# MCP23017.net
KiCad netlist of a schematic drawn in EAGLE
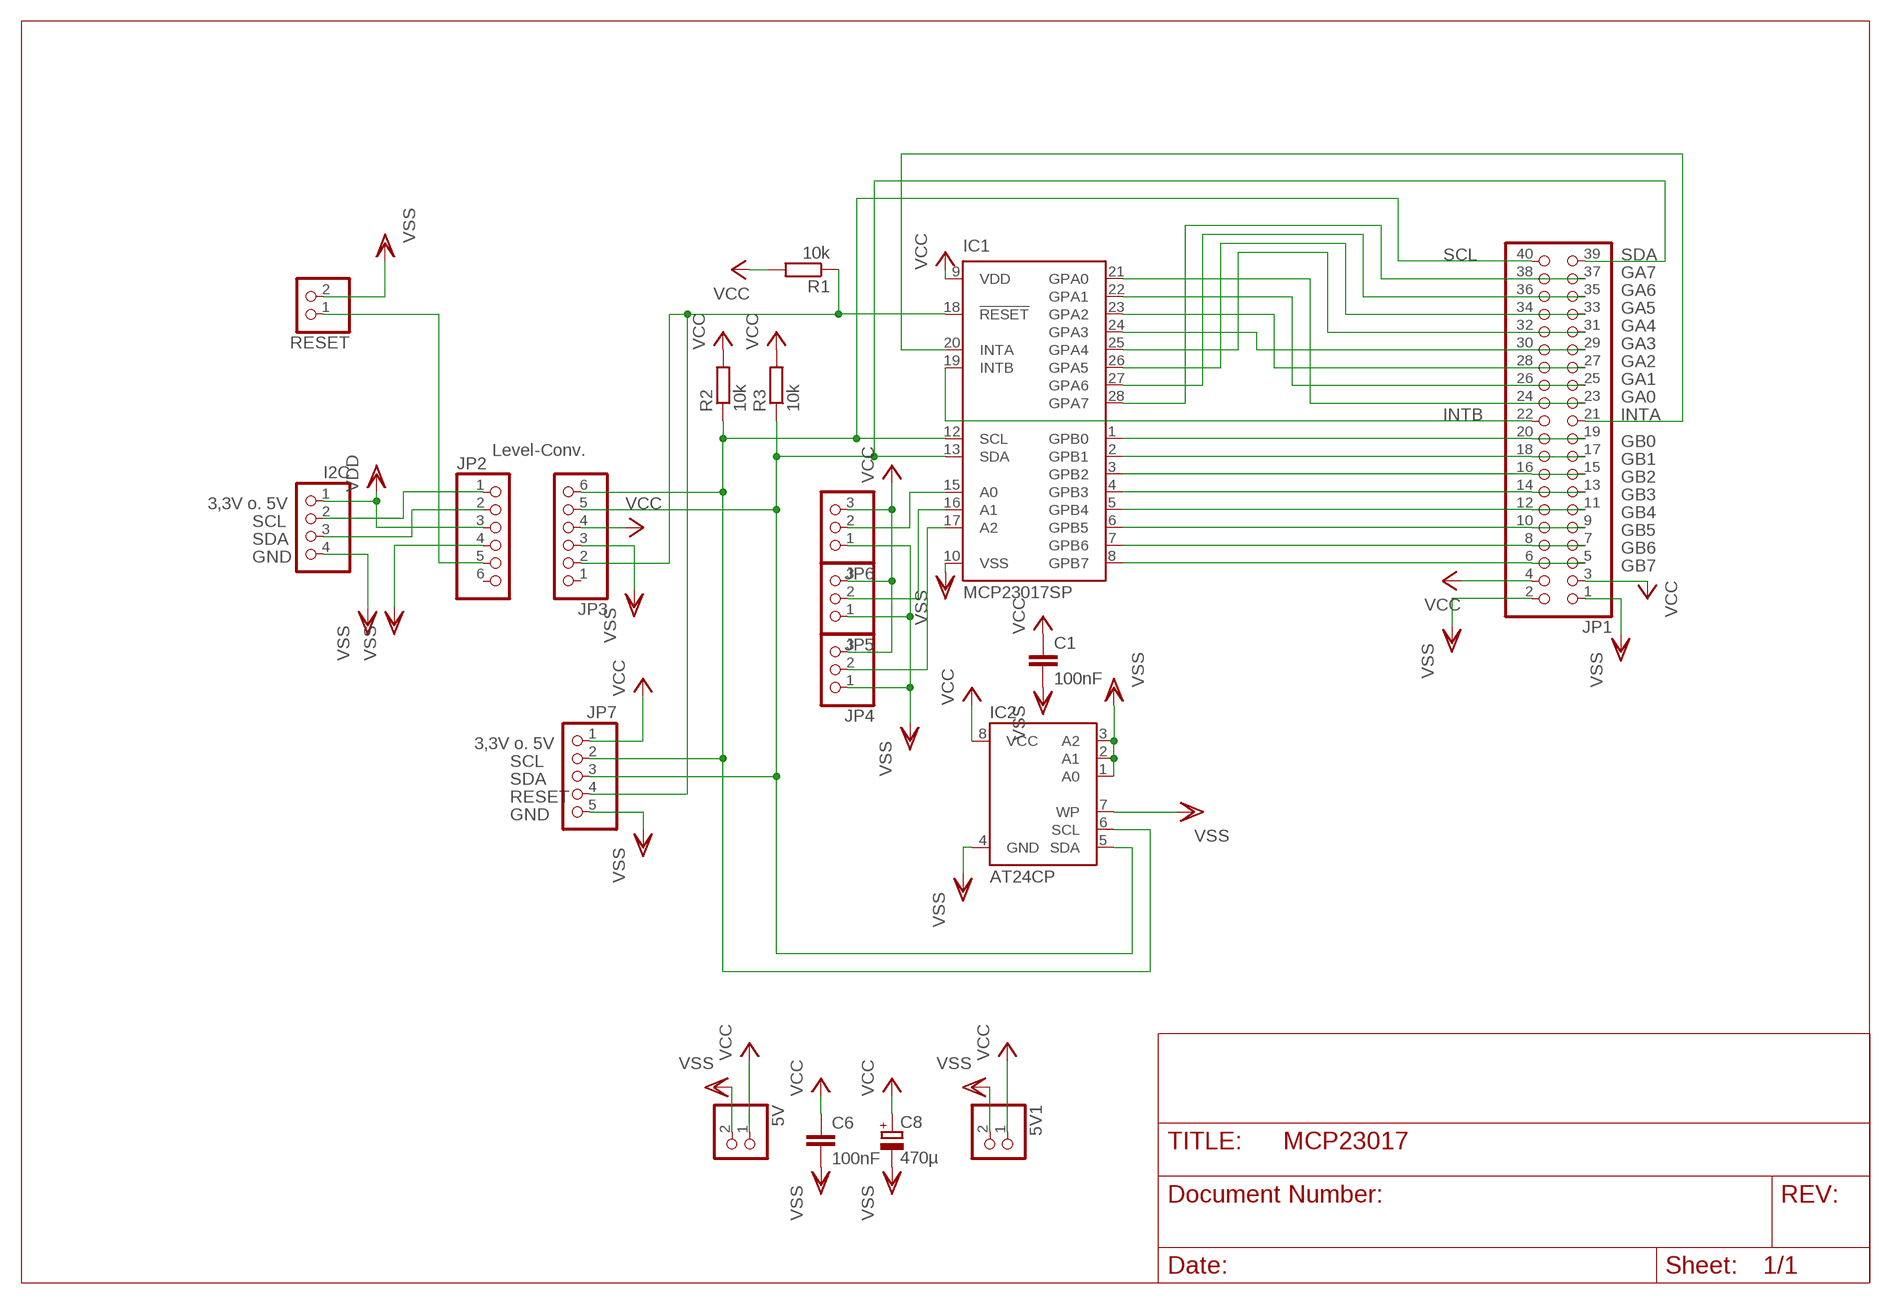
[diagram p0: schematic, sheet 1]

(export (version "E")
  (design (tool "Eeschema 10.0.6"))
  (components
    (comp (ref "5V")
      (value "PINHD-1X2")
      (footprint "eagle-import:1X02")
      (libsource (lib "eagle-import") (part "PINHD-1X2"))
    )
    (comp (ref "5V1")
      (value "PINHD-1X2")
      (footprint "eagle-import:1X02")
      (libsource (lib "eagle-import") (part "PINHD-1X2"))
    )
    (comp (ref "C1")
      (value "100nF")
      (footprint "eagle-import:C025-030X050")
      (libsource (lib "eagle-import") (part "C-EU025-030X050"))
    )
    (comp (ref "C6")
      (value "100nF")
      (footprint "eagle-import:C025-030X050")
      (libsource (lib "eagle-import") (part "C-EU025-030X050"))
    )
    (comp (ref "C8")
      (value "470µ")
      (footprint "eagle-import:E3,5-10")
      (libsource (lib "eagle-import") (part "CPOL-EUE3.5-10"))
    )
    (comp (ref "I2C")
      (value "PINHD-1X4")
      (footprint "eagle-import:1X04")
      (libsource (lib "eagle-import") (part "PINHD-1X4"))
    )
    (comp (ref "IC1")
      (value "MCP23017SP")
      (footprint "eagle-import:DIL28-3")
      (fields (field (name "MF") "MICROCHIP") (field (name "MPN") "MCP23017-E/SP"))
      (libsource (lib "eagle-import") (part "MCP23017SP"))
    )
    (comp (ref "IC2")
      (value "AT24CP")
      (footprint "eagle-import:DIL08")
      (fields (field (name "MPN") "AT24C1024BW-SH-B"))
      (libsource (lib "eagle-import") (part "AT24CP"))
    )
    (comp (ref "JP1")
      (value "PINHD-2X20")
      (footprint "eagle-import:2X20")
      (libsource (lib "eagle-import") (part "PINHD-2X20"))
    )
    (comp (ref "JP2")
      (value "PINHD-1X6")
      (footprint "eagle-import:1X06")
      (libsource (lib "eagle-import") (part "PINHD-1X6"))
    )
    (comp (ref "JP3")
      (value "PINHD-1X6")
      (footprint "eagle-import:1X06")
      (libsource (lib "eagle-import") (part "PINHD-1X6"))
    )
    (comp (ref "JP4")
      (value "PINHD-1X3")
      (footprint "eagle-import:1X03")
      (libsource (lib "eagle-import") (part "PINHD-1X3"))
    )
    (comp (ref "JP5")
      (value "PINHD-1X3")
      (footprint "eagle-import:1X03")
      (libsource (lib "eagle-import") (part "PINHD-1X3"))
    )
    (comp (ref "JP6")
      (value "PINHD-1X3")
      (footprint "eagle-import:1X03")
      (libsource (lib "eagle-import") (part "PINHD-1X3"))
    )
    (comp (ref "JP7")
      (value "PINHD-1X5")
      (footprint "eagle-import:1X05")
      (libsource (lib "eagle-import") (part "PINHD-1X5"))
    )
    (comp (ref "R1")
      (value "10k")
      (footprint "eagle-import:0207_10")
      (libsource (lib "eagle-import") (part "R-EU_0207/10"))
    )
    (comp (ref "R2")
      (value "10k")
      (footprint "eagle-import:0207_10")
      (libsource (lib "eagle-import") (part "R-EU_0207/10"))
    )
    (comp (ref "R3")
      (value "10k")
      (footprint "eagle-import:0207_10")
      (libsource (lib "eagle-import") (part "R-EU_0207/10"))
    )
    (comp (ref "RESET")
      (value "PINHD-1X2")
      (footprint "eagle-import:1X02")
      (libsource (lib "eagle-import") (part "PINHD-1X2"))
    )
  )
  (nets
    (net (code "1") (name "Net-(I2C-Pad2)") (class "Default")
      (node (ref "I2C") (pin "2") (pinfunction "2_2") (pintype "passive"))
      (node (ref "JP2") (pin "1") (pinfunction "1_1") (pintype "passive"))
    )
    (net (code "2") (name "Net-(I2C-Pad3)") (class "Default")
      (node (ref "I2C") (pin "3") (pinfunction "3_3") (pintype "passive"))
      (node (ref "JP2") (pin "2") (pinfunction "2_2") (pintype "passive"))
    )
    (net (code "3") (name "Net-(IC1-A0)") (class "Default")
      (node (ref "IC1") (pin "15") (pinfunction "A0_15") (pintype "input"))
      (node (ref "JP6") (pin "2") (pinfunction "2_2") (pintype "passive"))
    )
    (net (code "4") (name "Net-(IC1-A1)") (class "Default")
      (node (ref "IC1") (pin "16") (pinfunction "A1_16") (pintype "input"))
      (node (ref "JP5") (pin "2") (pinfunction "2_2") (pintype "passive"))
    )
    (net (code "5") (name "Net-(IC1-A2)") (class "Default")
      (node (ref "IC1") (pin "17") (pinfunction "A2_17") (pintype "input"))
      (node (ref "JP4") (pin "2") (pinfunction "2_2") (pintype "passive"))
    )
    (net (code "6") (name "Net-(IC1-GPA0)") (class "Default")
      (node (ref "IC1") (pin "21") (pinfunction "GPA0_21") (pintype "bidirectional"))
      (node (ref "JP1") (pin "23") (pinfunction "23_23") (pintype "passive"))
      (node (ref "JP1") (pin "24") (pinfunction "24_24") (pintype "passive"))
    )
    (net (code "7") (name "Net-(IC1-GPA1)") (class "Default")
      (node (ref "IC1") (pin "22") (pinfunction "GPA1_22") (pintype "bidirectional"))
      (node (ref "JP1") (pin "25") (pinfunction "25_25") (pintype "passive"))
      (node (ref "JP1") (pin "26") (pinfunction "26_26") (pintype "passive"))
    )
    (net (code "8") (name "Net-(IC1-GPA2)") (class "Default")
      (node (ref "IC1") (pin "23") (pinfunction "GPA2_23") (pintype "bidirectional"))
      (node (ref "JP1") (pin "27") (pinfunction "27_27") (pintype "passive"))
      (node (ref "JP1") (pin "28") (pinfunction "28_28") (pintype "passive"))
    )
    (net (code "9") (name "Net-(IC1-GPA3)") (class "Default")
      (node (ref "IC1") (pin "24") (pinfunction "GPA3_24") (pintype "bidirectional"))
      (node (ref "JP1") (pin "29") (pinfunction "29_29") (pintype "passive"))
      (node (ref "JP1") (pin "30") (pinfunction "30_30") (pintype "passive"))
    )
    (net (code "10") (name "Net-(IC1-GPA4)") (class "Default")
      (node (ref "IC1") (pin "25") (pinfunction "GPA4_25") (pintype "bidirectional"))
      (node (ref "JP1") (pin "31") (pinfunction "31_31") (pintype "passive"))
      (node (ref "JP1") (pin "32") (pinfunction "32_32") (pintype "passive"))
    )
    (net (code "11") (name "Net-(IC1-GPA5)") (class "Default")
      (node (ref "IC1") (pin "26") (pinfunction "GPA5_26") (pintype "bidirectional"))
      (node (ref "JP1") (pin "33") (pinfunction "33_33") (pintype "passive"))
      (node (ref "JP1") (pin "34") (pinfunction "34_34") (pintype "passive"))
    )
    (net (code "12") (name "Net-(IC1-GPA6)") (class "Default")
      (node (ref "IC1") (pin "27") (pinfunction "GPA6_27") (pintype "bidirectional"))
      (node (ref "JP1") (pin "35") (pinfunction "35_35") (pintype "passive"))
      (node (ref "JP1") (pin "36") (pinfunction "36_36") (pintype "passive"))
    )
    (net (code "13") (name "Net-(IC1-GPA7)") (class "Default")
      (node (ref "IC1") (pin "28") (pinfunction "GPA7_28") (pintype "bidirectional"))
      (node (ref "JP1") (pin "37") (pinfunction "37_37") (pintype "passive"))
      (node (ref "JP1") (pin "38") (pinfunction "38_38") (pintype "passive"))
    )
    (net (code "14") (name "Net-(IC1-GPB0)") (class "Default")
      (node (ref "IC1") (pin "1") (pinfunction "GPB0_1") (pintype "bidirectional"))
      (node (ref "JP1") (pin "19") (pinfunction "19_19") (pintype "passive"))
      (node (ref "JP1") (pin "20") (pinfunction "20_20") (pintype "passive"))
    )
    (net (code "15") (name "Net-(IC1-GPB1)") (class "Default")
      (node (ref "IC1") (pin "2") (pinfunction "GPB1_2") (pintype "bidirectional"))
      (node (ref "JP1") (pin "17") (pinfunction "17_17") (pintype "passive"))
      (node (ref "JP1") (pin "18") (pinfunction "18_18") (pintype "passive"))
    )
    (net (code "16") (name "Net-(IC1-GPB2)") (class "Default")
      (node (ref "IC1") (pin "3") (pinfunction "GPB2_3") (pintype "bidirectional"))
      (node (ref "JP1") (pin "15") (pinfunction "15_15") (pintype "passive"))
      (node (ref "JP1") (pin "16") (pinfunction "16_16") (pintype "passive"))
    )
    (net (code "17") (name "Net-(IC1-GPB3)") (class "Default")
      (node (ref "IC1") (pin "4") (pinfunction "GPB3_4") (pintype "bidirectional"))
      (node (ref "JP1") (pin "13") (pinfunction "13_13") (pintype "passive"))
      (node (ref "JP1") (pin "14") (pinfunction "14_14") (pintype "passive"))
    )
    (net (code "18") (name "Net-(IC1-GPB4)") (class "Default")
      (node (ref "IC1") (pin "5") (pinfunction "GPB4_5") (pintype "bidirectional"))
      (node (ref "JP1") (pin "11") (pinfunction "11_11") (pintype "passive"))
      (node (ref "JP1") (pin "12") (pinfunction "12_12") (pintype "passive"))
    )
    (net (code "19") (name "Net-(IC1-GPB5)") (class "Default")
      (node (ref "IC1") (pin "6") (pinfunction "GPB5_6") (pintype "bidirectional"))
      (node (ref "JP1") (pin "10") (pinfunction "10_10") (pintype "passive"))
      (node (ref "JP1") (pin "9") (pinfunction "9_9") (pintype "passive"))
    )
    (net (code "20") (name "Net-(IC1-GPB6)") (class "Default")
      (node (ref "IC1") (pin "7") (pinfunction "GPB6_7") (pintype "bidirectional"))
      (node (ref "JP1") (pin "7") (pinfunction "7_7") (pintype "passive"))
      (node (ref "JP1") (pin "8") (pinfunction "8_8") (pintype "passive"))
    )
    (net (code "21") (name "Net-(IC1-GPB7)") (class "Default")
      (node (ref "IC1") (pin "8") (pinfunction "GPB7_8") (pintype "bidirectional"))
      (node (ref "JP1") (pin "5") (pinfunction "5_5") (pintype "passive"))
      (node (ref "JP1") (pin "6") (pinfunction "6_6") (pintype "passive"))
    )
    (net (code "22") (name "Net-(IC1-INTA)") (class "Default")
      (node (ref "IC1") (pin "20") (pinfunction "INTA_20") (pintype "output"))
      (node (ref "JP1") (pin "21") (pinfunction "21_21") (pintype "passive"))
    )
    (net (code "23") (name "Net-(IC1-INTB)") (class "Default")
      (node (ref "IC1") (pin "19") (pinfunction "INTB_19") (pintype "output"))
      (node (ref "JP1") (pin "22") (pinfunction "22_22") (pintype "passive"))
    )
    (net (code "24") (name "Net-(IC1-SCL)") (class "Default")
      (node (ref "IC1") (pin "12") (pinfunction "SCL_12") (pintype "input"))
      (node (ref "IC2") (pin "6") (pinfunction "SCL_6") (pintype "bidirectional"))
      (node (ref "JP1") (pin "40") (pinfunction "40_40") (pintype "passive"))
      (node (ref "JP3") (pin "6") (pinfunction "6_6") (pintype "passive"))
      (node (ref "JP7") (pin "2") (pinfunction "2_2") (pintype "passive"))
      (node (ref "R2") (pin "1") (pinfunction "1_1") (pintype "passive"))
    )
    (net (code "25") (name "Net-(IC1-SDA)") (class "Default")
      (node (ref "IC1") (pin "13") (pinfunction "SDA_13") (pintype "bidirectional"))
      (node (ref "IC2") (pin "5") (pinfunction "SDA_5") (pintype "bidirectional"))
      (node (ref "JP1") (pin "39") (pinfunction "39_39") (pintype "passive"))
      (node (ref "JP3") (pin "5") (pinfunction "5_5") (pintype "passive"))
      (node (ref "JP7") (pin "3") (pinfunction "3_3") (pintype "passive"))
      (node (ref "R3") (pin "1") (pinfunction "1_1") (pintype "passive"))
    )
    (net (code "26") (name "Net-(IC1-~{RESET})") (class "Default")
      (node (ref "IC1") (pin "18") (pinfunction "~{RESET}_18") (pintype "input"))
      (node (ref "JP3") (pin "2") (pinfunction "2_2") (pintype "passive"))
      (node (ref "JP7") (pin "4") (pinfunction "4_4") (pintype "passive"))
      (node (ref "R1") (pin "1") (pinfunction "1_1") (pintype "passive"))
    )
    (net (code "27") (name "Net-(JP2-Pad5)") (class "Default")
      (node (ref "JP2") (pin "5") (pinfunction "5_5") (pintype "passive"))
      (node (ref "RESET") (pin "1") (pinfunction "1_1") (pintype "passive"))
    )
    (net (code "28") (name "VCC") (class "Default")
      (node (ref "5V") (pin "1") (pinfunction "1_1") (pintype "passive"))
      (node (ref "5V1") (pin "1") (pinfunction "1_1") (pintype "passive"))
      (node (ref "C1") (pin "1") (pinfunction "1_1") (pintype "passive"))
      (node (ref "C6") (pin "1") (pinfunction "1_1") (pintype "passive"))
      (node (ref "C8") (pin "+") (pinfunction "+_+") (pintype "passive"))
      (node (ref "IC1") (pin "9") (pinfunction "VDD_9") (pintype "power_in"))
      (node (ref "IC2") (pin "8") (pinfunction "VCC_8") (pintype "power_in"))
      (node (ref "JP1") (pin "3") (pinfunction "3_3") (pintype "passive"))
      (node (ref "JP1") (pin "4") (pinfunction "4_4") (pintype "passive"))
      (node (ref "JP3") (pin "4") (pinfunction "4_4") (pintype "passive"))
      (node (ref "JP4") (pin "3") (pinfunction "3_3") (pintype "passive"))
      (node (ref "JP5") (pin "3") (pinfunction "3_3") (pintype "passive"))
      (node (ref "JP6") (pin "3") (pinfunction "3_3") (pintype "passive"))
      (node (ref "JP7") (pin "1") (pinfunction "1_1") (pintype "passive"))
      (node (ref "R1") (pin "2") (pinfunction "2_2") (pintype "passive"))
      (node (ref "R2") (pin "2") (pinfunction "2_2") (pintype "passive"))
      (node (ref "R3") (pin "2") (pinfunction "2_2") (pintype "passive"))
    )
    (net (code "29") (name "VDD") (class "Default")
      (node (ref "I2C") (pin "1") (pinfunction "1_1") (pintype "passive"))
      (node (ref "JP2") (pin "3") (pinfunction "3_3") (pintype "passive"))
    )
    (net (code "30") (name "VSS") (class "Default")
      (node (ref "5V") (pin "2") (pinfunction "2_2") (pintype "passive"))
      (node (ref "5V1") (pin "2") (pinfunction "2_2") (pintype "passive"))
      (node (ref "C1") (pin "2") (pinfunction "2_2") (pintype "passive"))
      (node (ref "C6") (pin "2") (pinfunction "2_2") (pintype "passive"))
      (node (ref "C8") (pin "-") (pinfunction "-_-") (pintype "passive"))
      (node (ref "I2C") (pin "4") (pinfunction "4_4") (pintype "passive"))
      (node (ref "IC1") (pin "10") (pinfunction "VSS_10") (pintype "power_in"))
      (node (ref "IC2") (pin "1") (pinfunction "A0_1") (pintype "input"))
      (node (ref "IC2") (pin "2") (pinfunction "A1_2") (pintype "input"))
      (node (ref "IC2") (pin "3") (pinfunction "A2_3") (pintype "input"))
      (node (ref "IC2") (pin "4") (pinfunction "GND_4") (pintype "power_in"))
      (node (ref "IC2") (pin "7") (pinfunction "WP_7") (pintype "input"))
      (node (ref "JP1") (pin "1") (pinfunction "1_1") (pintype "passive"))
      (node (ref "JP1") (pin "2") (pinfunction "2_2") (pintype "passive"))
      (node (ref "JP2") (pin "4") (pinfunction "4_4") (pintype "passive"))
      (node (ref "JP3") (pin "3") (pinfunction "3_3") (pintype "passive"))
      (node (ref "JP4") (pin "1") (pinfunction "1_1") (pintype "passive"))
      (node (ref "JP5") (pin "1") (pinfunction "1_1") (pintype "passive"))
      (node (ref "JP6") (pin "1") (pinfunction "1_1") (pintype "passive"))
      (node (ref "JP7") (pin "5") (pinfunction "5_5") (pintype "passive"))
      (node (ref "RESET") (pin "2") (pinfunction "2_2") (pintype "passive"))
    )
    (net (code "31") (name "unconnected-(JP2-Pad6)") (class "Default")
      (node (ref "JP2") (pin "6") (pinfunction "6_6") (pintype "passive"))
    )
    (net (code "32") (name "unconnected-(JP3-Pad1)") (class "Default")
      (node (ref "JP3") (pin "1") (pinfunction "1_1") (pintype "passive"))
    )
  )
)
